# Filtro_Fonte.net
KiCad netlist of a schematic drawn in Altium Designer
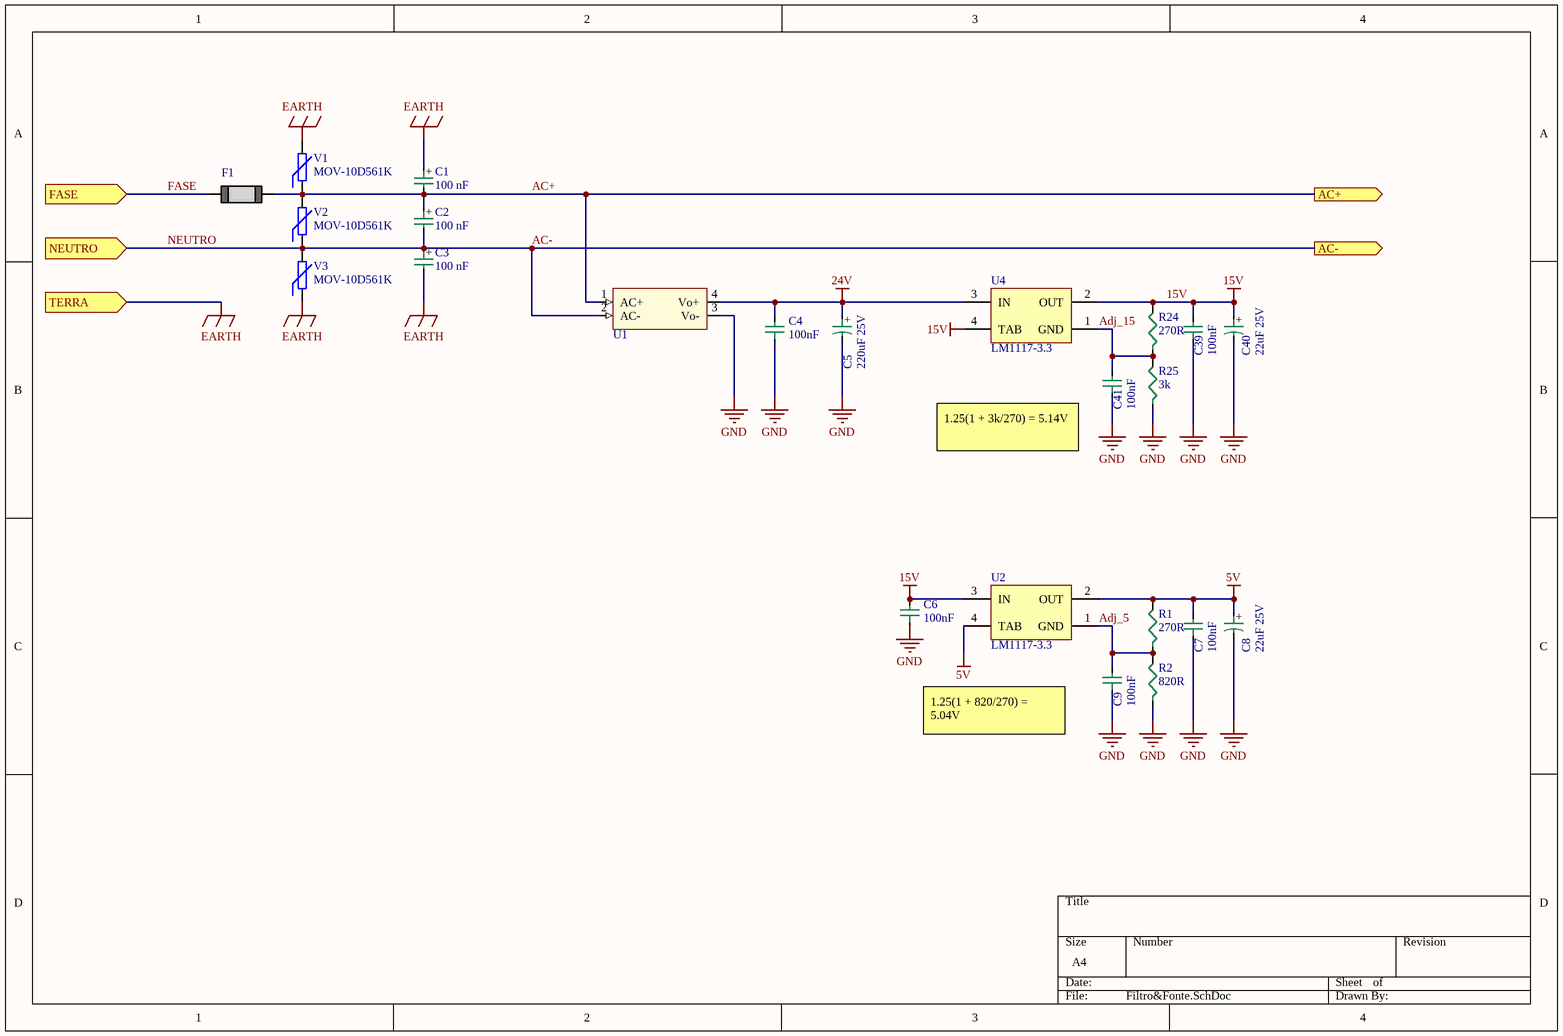
[diagram p0: Filtro&Fonte.SchDoc]

(export (version "E")
  (design (tool "Eeschema 10.0.6"))
  (components
    (comp (ref "C1")
      (value "100 nF")
      (footprint "CAP FILM 10 mm Lead")
      (description "Safety Capacitors 275VAC 0.1uF 10% LS 10mm X2")
      (fields (field (name "Comment") "Cap Film 22.5mm"))
      (libsource (lib "RLC_Integrated_Library") (part "Capacitor FILM 100nF 275 VAc"))
    )
    (comp (ref "C2")
      (value "100 nF")
      (footprint "CAP FILM 10 mm Lead")
      (description "Safety Capacitors 275VAC 0.1uF 10% LS 10mm X2")
      (fields (field (name "Comment") "Cap Film 22.5mm"))
      (libsource (lib "RLC_Integrated_Library") (part "Capacitor FILM 100nF 275 VAc"))
    )
    (comp (ref "C3")
      (value "100 nF")
      (footprint "CAP FILM 10 mm Lead")
      (description "Safety Capacitors 275VAC 0.1uF 10% LS 10mm X2")
      (fields (field (name "Comment") "Cap Film 22.5mm"))
      (libsource (lib "RLC_Integrated_Library") (part "Capacitor FILM 100nF 275 VAc"))
    )
    (comp (ref "C4")
      (value "100nF")
      (footprint "0805C")
      (description "Capacitor SMD 0805")
      (fields (field (name "Comment") "0805"))
      (libsource (lib "RLC_Integrated_Library") (part "Capacitor SMD 0805"))
    )
    (comp (ref "C5")
      (value "220uF 25V")
      (footprint "CAP SMD D8.0 A10.2")
      (description "Capacitor SMD D8.0 A10.2")
      (fields (field (name "Comment") "D8.0 A10.2"))
      (libsource (lib "RLC_Integrated_Library") (part "Capacitor SMD D8.0 A10.2"))
    )
    (comp (ref "C6")
      (value "100nF")
      (footprint "0805C")
      (description "Capacitor SMD 0805")
      (fields (field (name "Comment") "0805"))
      (libsource (lib "RLC_Integrated_Library") (part "Capacitor SMD 0805"))
    )
    (comp (ref "C7")
      (value "100nF")
      (footprint "0805C")
      (description "Capacitor SMD 0805")
      (fields (field (name "Comment") "0805"))
      (libsource (lib "RLC_Integrated_Library") (part "Capacitor SMD 0805"))
    )
    (comp (ref "C8")
      (value "22uF 25V")
      (footprint "CAP SMD D5.0 A5.4")
      (description "Capacitor SMD D5.0 A5.4")
      (fields (field (name "Comment") "D5.0 A5.4"))
      (libsource (lib "RLC_Integrated_Library") (part "Capacitor SMD D5.0 A5.4"))
    )
    (comp (ref "C9")
      (value "100nF")
      (footprint "0805C")
      (description "Capacitor SMD 0805")
      (fields (field (name "Comment") "0805"))
      (libsource (lib "RLC_Integrated_Library") (part "Capacitor SMD 0805"))
    )
    (comp (ref "C39")
      (value "100nF")
      (footprint "0805C")
      (description "Capacitor SMD 0805")
      (fields (field (name "Comment") "0805"))
      (libsource (lib "RLC_Integrated_Library") (part "Capacitor SMD 0805"))
    )
    (comp (ref "C40")
      (value "22uF 25V")
      (footprint "CAP SMD D5.0 A5.4")
      (description "Capacitor SMD D5.0 A5.4")
      (fields (field (name "Comment") "D5.0 A5.4"))
      (libsource (lib "RLC_Integrated_Library") (part "Capacitor SMD D5.0 A5.4"))
    )
    (comp (ref "C41")
      (value "100nF")
      (footprint "0805C")
      (description "Capacitor SMD 0805")
      (fields (field (name "Comment") "0805"))
      (libsource (lib "RLC_Integrated_Library") (part "Capacitor SMD 0805"))
    )
    (comp (ref "F1")
      (value "5 x 20 mm")
      (footprint "Fuseholder 5 x 20 mm")
      (description "Fuseholder Open Design, 5 x 20 mm")
      (libsource (lib "Jose_lib") (part "FuseHolder 5 x 20 mm"))
    )
    (comp (ref "R1")
      (value "270R")
      (footprint "0805")
      (description "Resistor SMD 0805 1/8 W")
      (fields (field (name "Comment") "0805"))
      (libsource (lib "RLC_Integrated_Library") (part "Resistor SMD 0805 1/8 W"))
    )
    (comp (ref "R2")
      (value "820R")
      (footprint "0805")
      (description "Resistor SMD 0805 1/8 W")
      (fields (field (name "Comment") "0805"))
      (libsource (lib "RLC_Integrated_Library") (part "Resistor SMD 0805 1/8 W"))
    )
    (comp (ref "R24")
      (value "270R")
      (footprint "0805")
      (description "Resistor SMD 0805 1/8 W")
      (fields (field (name "Comment") "0805"))
      (libsource (lib "RLC_Integrated_Library") (part "Resistor SMD 0805 1/8 W"))
    )
    (comp (ref "R25")
      (value "3k")
      (footprint "0805")
      (description "Resistor SMD 0805 1/8 W")
      (fields (field (name "Comment") "0805"))
      (libsource (lib "RLC_Integrated_Library") (part "Resistor SMD 0805 1/8 W"))
    )
    (comp (ref "U1")
      (value "5V supply*")
      (footprint "HILINK")
      (description "5V 3W Ultra-small Power Module PM03")
      (libsource (lib "Jose_lib") (part "HI-LINK PM01 3W"))
    )
    (comp (ref "U2")
      (value "LM1117-3.3")
      (footprint "LM1117")
      (description "CI Regulador LM1117IMP-3.3 800mA Low-Dropout Linear Regulator, 4-pin SOT-223")
      (fields
        (field (name "PARTNUMBER") "LM1117IMP-3.3")
        (field (name "MANUFACTURER") "National Semiconductor")
        (field (name "PUBLISHER") "Altium Limited")
      )
      (libsource (lib "CI_Integrated_Library") (part "LM1117IMP-3.3"))
    )
    (comp (ref "U4")
      (value "LM1117-3.3")
      (footprint "LM1117")
      (description "CI Regulador LM1117IMP-3.3 800mA Low-Dropout Linear Regulator, 4-pin SOT-223")
      (fields
        (field (name "PARTNUMBER") "LM1117IMP-3.3")
        (field (name "MANUFACTURER") "National Semiconductor")
        (field (name "PUBLISHER") "Altium Limited")
      )
      (libsource (lib "CI_Integrated_Library") (part "LM1117IMP-3.3"))
    )
    (comp (ref "V1")
      (value "MOV-10D561K")
      (footprint "VARISTOR 7.5mm")
      (description "Varistors 180pF 560volts 10%")
      (libsource (lib "Jose_lib") (part "Varistor"))
    )
    (comp (ref "V2")
      (value "MOV-10D561K")
      (footprint "VARISTOR 7.5mm")
      (description "Varistors 180pF 560volts 10%")
      (libsource (lib "Jose_lib") (part "Varistor"))
    )
    (comp (ref "V3")
      (value "MOV-10D561K")
      (footprint "VARISTOR 7.5mm")
      (description "Varistors 180pF 560volts 10%")
      (libsource (lib "Jose_lib") (part "Varistor"))
    )
  )
  (nets
    (net (code "1") (name "/AC+") (class "Default")
      (node (ref "C1") (pin "2") (pinfunction "2_2") (pintype "passive"))
      (node (ref "C2") (pin "1") (pinfunction "1_1") (pintype "passive"))
      (node (ref "F1") (pin "1") (pinfunction "1_1") (pintype "passive"))
      (node (ref "U1") (pin "1") (pinfunction "AC+_1") (pintype "input"))
      (node (ref "V1") (pin "1") (pinfunction "1_1") (pintype "passive"))
      (node (ref "V2") (pin "2") (pinfunction "2_2") (pintype "passive"))
    )
    (net (code "2") (name "/AC-") (class "Default")
      (node (ref "C2") (pin "2") (pinfunction "2_2") (pintype "passive"))
      (node (ref "C3") (pin "1") (pinfunction "1_1") (pintype "passive"))
      (node (ref "U1") (pin "2") (pinfunction "AC-_2") (pintype "input"))
      (node (ref "V2") (pin "1") (pinfunction "1_1") (pintype "passive"))
      (node (ref "V3") (pin "2") (pinfunction "2_2") (pintype "passive"))
    )
    (net (code "3") (name "/Adj_5") (class "Default")
      (node (ref "C9") (pin "2") (pinfunction "2_2") (pintype "passive"))
      (node (ref "R1") (pin "1") (pinfunction "1_1") (pintype "passive"))
      (node (ref "R2") (pin "2") (pinfunction "2_2") (pintype "passive"))
      (node (ref "U2") (pin "1") (pinfunction "GND_1") (pintype "power_in"))
    )
    (net (code "4") (name "/Adj_15") (class "Default")
      (node (ref "C41") (pin "2") (pinfunction "2_2") (pintype "passive"))
      (node (ref "R24") (pin "1") (pinfunction "1_1") (pintype "passive"))
      (node (ref "R25") (pin "2") (pinfunction "2_2") (pintype "passive"))
      (node (ref "U4") (pin "1") (pinfunction "GND_1") (pintype "power_in"))
    )
    (net (code "5") (name "/FASE") (class "Default")
      (node (ref "F1") (pin "2") (pinfunction "2_2") (pintype "passive"))
    )
    (net (code "6") (name "5V") (class "Default")
      (node (ref "C7") (pin "2") (pinfunction "2_2") (pintype "passive"))
      (node (ref "C8") (pin "1") (pinfunction "1_1") (pintype "passive"))
      (node (ref "R1") (pin "2") (pinfunction "2_2") (pintype "passive"))
      (node (ref "U2") (pin "2") (pinfunction "OUT_2") (pintype "power_in"))
      (node (ref "U2") (pin "4") (pinfunction "TAB_4") (pintype "power_in"))
    )
    (net (code "7") (name "15V") (class "Default")
      (node (ref "C39") (pin "2") (pinfunction "2_2") (pintype "passive"))
      (node (ref "C40") (pin "1") (pinfunction "1_1") (pintype "passive"))
      (node (ref "C6") (pin "2") (pinfunction "2_2") (pintype "passive"))
      (node (ref "R24") (pin "2") (pinfunction "2_2") (pintype "passive"))
      (node (ref "U2") (pin "3") (pinfunction "IN_3") (pintype "power_in"))
      (node (ref "U4") (pin "2") (pinfunction "OUT_2") (pintype "power_in"))
      (node (ref "U4") (pin "4") (pinfunction "TAB_4") (pintype "power_in"))
    )
    (net (code "8") (name "24V") (class "Default")
      (node (ref "C4") (pin "2") (pinfunction "2_2") (pintype "passive"))
      (node (ref "C5") (pin "1") (pinfunction "1_1") (pintype "passive"))
      (node (ref "U1") (pin "4") (pinfunction "Vo+_4") (pintype "power_in"))
      (node (ref "U4") (pin "3") (pinfunction "IN_3") (pintype "power_in"))
    )
    (net (code "9") (name "EARTH") (class "Default")
      (node (ref "C1") (pin "1") (pinfunction "1_1") (pintype "passive"))
      (node (ref "C3") (pin "2") (pinfunction "2_2") (pintype "passive"))
      (node (ref "V1") (pin "2") (pinfunction "2_2") (pintype "passive"))
      (node (ref "V3") (pin "1") (pinfunction "1_1") (pintype "passive"))
    )
    (net (code "10") (name "GND") (class "Default")
      (node (ref "C39") (pin "1") (pinfunction "1_1") (pintype "passive"))
      (node (ref "C4") (pin "1") (pinfunction "1_1") (pintype "passive"))
      (node (ref "C40") (pin "2") (pinfunction "2_2") (pintype "passive"))
      (node (ref "C41") (pin "1") (pinfunction "1_1") (pintype "passive"))
      (node (ref "C5") (pin "2") (pinfunction "2_2") (pintype "passive"))
      (node (ref "C6") (pin "1") (pinfunction "1_1") (pintype "passive"))
      (node (ref "C7") (pin "1") (pinfunction "1_1") (pintype "passive"))
      (node (ref "C8") (pin "2") (pinfunction "2_2") (pintype "passive"))
      (node (ref "C9") (pin "1") (pinfunction "1_1") (pintype "passive"))
      (node (ref "R2") (pin "1") (pinfunction "1_1") (pintype "passive"))
      (node (ref "R25") (pin "1") (pinfunction "1_1") (pintype "passive"))
      (node (ref "U1") (pin "3") (pinfunction "Vo-_3") (pintype "power_in"))
    )
  )
)
